# motorController.net
KiCad netlist of a schematic drawn in Altium Designer
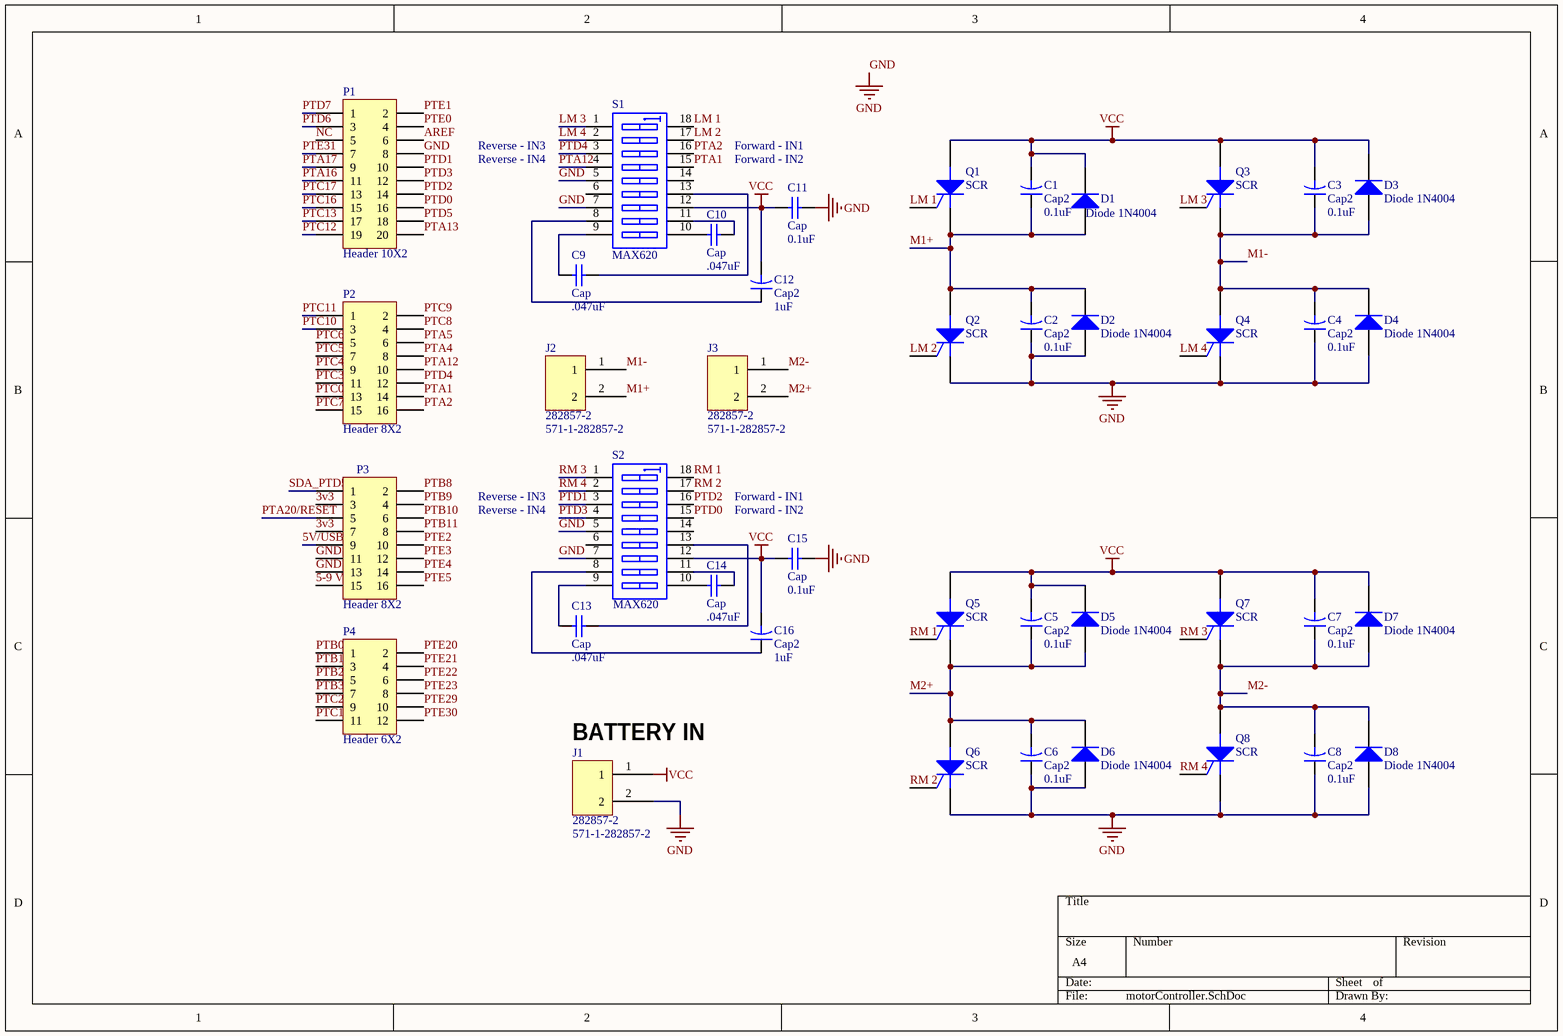
[diagram p0: motorController.SchDoc]

(export (version "E")
  (design (tool "Eeschema 10.0.6"))
  (components
    (comp (ref "C1")
      (value "Cap2")
      (footprint "CAPR5-4X5")
      (description "Capacitor")
      (fields (field (name "ALTIUM_VALUE") "0.1uF") (field (name "PUBLISHER") "Altium Limited"))
      (libsource (lib "Miscellaneous Devices") (part "Cap2"))
    )
    (comp (ref "C2")
      (value "Cap2")
      (footprint "CAPR5-4X5")
      (description "Capacitor")
      (fields (field (name "ALTIUM_VALUE") "0.1uF") (field (name "PUBLISHER") "Altium Limited"))
      (libsource (lib "Miscellaneous Devices") (part "Cap2"))
    )
    (comp (ref "C3")
      (value "Cap2")
      (footprint "CAPR5-4X5")
      (description "Capacitor")
      (fields (field (name "ALTIUM_VALUE") "0.1uF") (field (name "PUBLISHER") "Altium Limited"))
      (libsource (lib "Miscellaneous Devices") (part "Cap2"))
    )
    (comp (ref "C4")
      (value "Cap2")
      (footprint "CAPR5-4X5")
      (description "Capacitor")
      (fields (field (name "ALTIUM_VALUE") "0.1uF") (field (name "PUBLISHER") "Altium Limited"))
      (libsource (lib "Miscellaneous Devices") (part "Cap2"))
    )
    (comp (ref "C5")
      (value "Cap2")
      (footprint "CAPR5-4X5")
      (description "Capacitor")
      (fields (field (name "ALTIUM_VALUE") "0.1uF") (field (name "PUBLISHER") "Altium Limited"))
      (libsource (lib "Miscellaneous Devices") (part "Cap2"))
    )
    (comp (ref "C6")
      (value "Cap2")
      (footprint "CAPR5-4X5")
      (description "Capacitor")
      (fields (field (name "ALTIUM_VALUE") "0.1uF") (field (name "PUBLISHER") "Altium Limited"))
      (libsource (lib "Miscellaneous Devices") (part "Cap2"))
    )
    (comp (ref "C7")
      (value "Cap2")
      (footprint "CAPR5-4X5")
      (description "Capacitor")
      (fields (field (name "ALTIUM_VALUE") "0.1uF") (field (name "PUBLISHER") "Altium Limited"))
      (libsource (lib "Miscellaneous Devices") (part "Cap2"))
    )
    (comp (ref "C8")
      (value "Cap2")
      (footprint "CAPR5-4X5")
      (description "Capacitor")
      (fields (field (name "ALTIUM_VALUE") "0.1uF") (field (name "PUBLISHER") "Altium Limited"))
      (libsource (lib "Miscellaneous Devices") (part "Cap2"))
    )
    (comp (ref "C9")
      (value "Cap")
      (footprint "RAD-0.3")
      (description "Capacitor")
      (fields (field (name "ALTIUM_VALUE") ".047uF") (field (name "PUBLISHER") "Altium Limited"))
      (libsource (lib "Miscellaneous Devices") (part "Cap"))
    )
    (comp (ref "C10")
      (value "Cap")
      (footprint "RAD-0.3")
      (description "Capacitor")
      (fields (field (name "ALTIUM_VALUE") ".047uF") (field (name "PUBLISHER") "Altium Limited"))
      (libsource (lib "Miscellaneous Devices") (part "Cap"))
    )
    (comp (ref "C11")
      (value "Cap")
      (footprint "RAD-0.3")
      (description "Capacitor")
      (fields (field (name "ALTIUM_VALUE") "0.1uF") (field (name "PUBLISHER") "Altium Limited"))
      (libsource (lib "Miscellaneous Devices") (part "Cap"))
    )
    (comp (ref "C12")
      (value "Cap2")
      (footprint "CAPR5-4X5")
      (description "Capacitor")
      (fields (field (name "ALTIUM_VALUE") "1uF") (field (name "PUBLISHER") "Altium Limited"))
      (libsource (lib "Miscellaneous Devices") (part "Cap2"))
    )
    (comp (ref "C13")
      (value "Cap")
      (footprint "RAD-0.3")
      (description "Capacitor")
      (fields (field (name "ALTIUM_VALUE") ".047uF") (field (name "PUBLISHER") "Altium Limited"))
      (libsource (lib "Miscellaneous Devices") (part "Cap"))
    )
    (comp (ref "C14")
      (value "Cap")
      (footprint "RAD-0.3")
      (description "Capacitor")
      (fields (field (name "ALTIUM_VALUE") ".047uF") (field (name "PUBLISHER") "Altium Limited"))
      (libsource (lib "Miscellaneous Devices") (part "Cap"))
    )
    (comp (ref "C15")
      (value "Cap")
      (footprint "RAD-0.3")
      (description "Capacitor")
      (fields (field (name "ALTIUM_VALUE") "0.1uF") (field (name "PUBLISHER") "Altium Limited"))
      (libsource (lib "Miscellaneous Devices") (part "Cap"))
    )
    (comp (ref "C16")
      (value "Cap2")
      (footprint "CAPR5-4X5")
      (description "Capacitor")
      (fields (field (name "ALTIUM_VALUE") "1uF") (field (name "PUBLISHER") "Altium Limited"))
      (libsource (lib "Miscellaneous Devices") (part "Cap2"))
    )
    (comp (ref "D1")
      (value "Diode 1N4004")
      (footprint "DO-41")
      (description "1 Amp General Purpose Rectifier")
      (fields (field (name "PUBLISHER") "Altium Limited"))
      (libsource (lib "Miscellaneous Devices") (part "Diode 1N4004"))
    )
    (comp (ref "D2")
      (value "Diode 1N4004")
      (footprint "DO-41")
      (description "1 Amp General Purpose Rectifier")
      (fields (field (name "PUBLISHER") "Altium Limited"))
      (libsource (lib "Miscellaneous Devices") (part "Diode 1N4004"))
    )
    (comp (ref "D3")
      (value "Diode 1N4004")
      (footprint "DO-41")
      (description "1 Amp General Purpose Rectifier")
      (fields (field (name "PUBLISHER") "Altium Limited"))
      (libsource (lib "Miscellaneous Devices") (part "Diode 1N4004"))
    )
    (comp (ref "D4")
      (value "Diode 1N4004")
      (footprint "DO-41")
      (description "1 Amp General Purpose Rectifier")
      (fields (field (name "PUBLISHER") "Altium Limited"))
      (libsource (lib "Miscellaneous Devices") (part "Diode 1N4004"))
    )
    (comp (ref "D5")
      (value "Diode 1N4004")
      (footprint "DO-41")
      (description "1 Amp General Purpose Rectifier")
      (fields (field (name "PUBLISHER") "Altium Limited"))
      (libsource (lib "Miscellaneous Devices") (part "Diode 1N4004"))
    )
    (comp (ref "D6")
      (value "Diode 1N4004")
      (footprint "DO-41")
      (description "1 Amp General Purpose Rectifier")
      (fields (field (name "PUBLISHER") "Altium Limited"))
      (libsource (lib "Miscellaneous Devices") (part "Diode 1N4004"))
    )
    (comp (ref "D7")
      (value "Diode 1N4004")
      (footprint "DO-41")
      (description "1 Amp General Purpose Rectifier")
      (fields (field (name "PUBLISHER") "Altium Limited"))
      (libsource (lib "Miscellaneous Devices") (part "Diode 1N4004"))
    )
    (comp (ref "D8")
      (value "Diode 1N4004")
      (footprint "DO-41")
      (description "1 Amp General Purpose Rectifier")
      (fields (field (name "PUBLISHER") "Altium Limited"))
      (libsource (lib "Miscellaneous Devices") (part "Diode 1N4004"))
    )
    (comp (ref "J1")
      (value "282857-2")
      (footprint "282857-2")
      (fields (field (name "SUPPLIER PART NUMBER 1") "571-1-282857-2"))
      (libsource (lib "TE_Connectors") (part "282857-2"))
    )
    (comp (ref "J2")
      (value "282857-2")
      (footprint "282857-2")
      (fields (field (name "SUPPLIER PART NUMBER 1") "571-1-282857-2"))
      (libsource (lib "TE_Connectors") (part "282857-2"))
    )
    (comp (ref "J3")
      (value "282857-2")
      (footprint "282857-2")
      (fields (field (name "SUPPLIER PART NUMBER 1") "571-1-282857-2"))
      (libsource (lib "TE_Connectors") (part "282857-2"))
    )
    (comp (ref "P1")
      (value "Header 10X2")
      (footprint "HDR2X10")
      (description "Header, 10-Pin, Dual row")
      (fields (field (name "PUBLISHER") "Altium Limited"))
      (libsource (lib "Miscellaneous Connectors") (part "Header 10X2"))
    )
    (comp (ref "P2")
      (value "Header 8X2")
      (footprint "HDR2X8")
      (description "Header, 8-Pin, Dual row")
      (fields (field (name "PUBLISHER") "Altium Limited"))
      (libsource (lib "Miscellaneous Connectors") (part "Header 8X2"))
    )
    (comp (ref "P3")
      (value "Header 8X2")
      (footprint "HDR2X8")
      (description "Header, 8-Pin, Dual row")
      (fields (field (name "PUBLISHER") "Altium Limited"))
      (libsource (lib "Miscellaneous Connectors") (part "Header 8X2"))
    )
    (comp (ref "P4")
      (value "Header 6X2")
      (footprint "HDR2X6")
      (description "Header, 6-Pin, Dual row")
      (fields (field (name "PUBLISHER") "Altium Limited"))
      (libsource (lib "Miscellaneous Connectors") (part "Header 6X2"))
    )
    (comp (ref "Q1")
      (value "SCR")
      (footprint "TO-220-AB")
      (description "Silicon Controlled Rectifier")
      (fields (field (name "PUBLISHER") "Altium Limited"))
      (libsource (lib "Miscellaneous Devices") (part "SCR"))
    )
    (comp (ref "Q2")
      (value "SCR")
      (footprint "TO-220-AB")
      (description "Silicon Controlled Rectifier")
      (fields (field (name "PUBLISHER") "Altium Limited"))
      (libsource (lib "Miscellaneous Devices") (part "SCR"))
    )
    (comp (ref "Q3")
      (value "SCR")
      (footprint "TO-220-AB")
      (description "Silicon Controlled Rectifier")
      (fields (field (name "PUBLISHER") "Altium Limited"))
      (libsource (lib "Miscellaneous Devices") (part "SCR"))
    )
    (comp (ref "Q4")
      (value "SCR")
      (footprint "TO-220-AB")
      (description "Silicon Controlled Rectifier")
      (fields (field (name "PUBLISHER") "Altium Limited"))
      (libsource (lib "Miscellaneous Devices") (part "SCR"))
    )
    (comp (ref "Q5")
      (value "SCR")
      (footprint "TO-220-AB")
      (description "Silicon Controlled Rectifier")
      (fields (field (name "PUBLISHER") "Altium Limited"))
      (libsource (lib "Miscellaneous Devices") (part "SCR"))
    )
    (comp (ref "Q6")
      (value "SCR")
      (footprint "TO-220-AB")
      (description "Silicon Controlled Rectifier")
      (fields (field (name "PUBLISHER") "Altium Limited"))
      (libsource (lib "Miscellaneous Devices") (part "SCR"))
    )
    (comp (ref "Q7")
      (value "SCR")
      (footprint "TO-220-AB")
      (description "Silicon Controlled Rectifier")
      (fields (field (name "PUBLISHER") "Altium Limited"))
      (libsource (lib "Miscellaneous Devices") (part "SCR"))
    )
    (comp (ref "Q8")
      (value "SCR")
      (footprint "TO-220-AB")
      (description "Silicon Controlled Rectifier")
      (fields (field (name "PUBLISHER") "Altium Limited"))
      (libsource (lib "Miscellaneous Devices") (part "SCR"))
    )
    (comp (ref "S1")
      (value "MAX620")
      (footprint "DIP-18")
      (description "DIP Switch, 9 Position, SPST")
      (fields (field (name "PUBLISHER") "Altium Limited"))
      (libsource (lib "Miscellaneous Devices") (part "SW DIP-9"))
    )
    (comp (ref "S2")
      (value "MAX620")
      (footprint "DIP-18")
      (description "DIP Switch, 9 Position, SPST")
      (fields (field (name "PUBLISHER") "Altium Limited"))
      (libsource (lib "Miscellaneous Devices") (part "SW DIP-9"))
    )
  )
  (nets
    (net (code "1") (name "/3v3") (class "Default")
      (node (ref "P3") (pin "3") (pinfunction "3_3") (pintype "passive"))
      (node (ref "P3") (pin "7") (pinfunction "7_7") (pintype "passive"))
    )
    (net (code "2") (name "/5-9 Vin") (class "Default")
      (node (ref "P3") (pin "15") (pinfunction "15_15") (pintype "passive"))
    )
    (net (code "3") (name "/5V{slash}USB") (class "Default")
      (node (ref "P3") (pin "9") (pinfunction "9_9") (pintype "passive"))
    )
    (net (code "4") (name "/AREF") (class "Default")
      (node (ref "P1") (pin "6") (pinfunction "6_6") (pintype "passive"))
    )
    (net (code "5") (name "/LM 1") (class "Default")
      (node (ref "Q1") (pin "2") (pinfunction "G_2") (pintype "passive"))
      (node (ref "S1") (pin "18") (pinfunction "B1_18") (pintype "passive"))
    )
    (net (code "6") (name "/LM 2") (class "Default")
      (node (ref "Q2") (pin "2") (pinfunction "G_2") (pintype "passive"))
      (node (ref "S1") (pin "17") (pinfunction "B2_17") (pintype "passive"))
    )
    (net (code "7") (name "/LM 3") (class "Default")
      (node (ref "Q3") (pin "2") (pinfunction "G_2") (pintype "passive"))
      (node (ref "S1") (pin "1") (pinfunction "A1_1") (pintype "passive"))
    )
    (net (code "8") (name "/LM 4") (class "Default")
      (node (ref "Q4") (pin "2") (pinfunction "G_2") (pintype "passive"))
      (node (ref "S1") (pin "2") (pinfunction "A2_2") (pintype "passive"))
    )
    (net (code "9") (name "/M1+") (class "Default")
      (node (ref "C1") (pin "1") (pinfunction "1_1") (pintype "passive"))
      (node (ref "C2") (pin "2") (pinfunction "2_2") (pintype "passive"))
      (node (ref "D1") (pin "1") (pinfunction "A_1") (pintype "passive"))
      (node (ref "D2") (pin "2") (pinfunction "K_2") (pintype "passive"))
      (node (ref "J2") (pin "2") (pinfunction "2_2") (pintype "passive"))
      (node (ref "Q1") (pin "3") (pinfunction "K_3") (pintype "passive"))
      (node (ref "Q2") (pin "1") (pinfunction "A_1") (pintype "passive"))
    )
    (net (code "10") (name "/M1-") (class "Default")
      (node (ref "C3") (pin "1") (pinfunction "1_1") (pintype "passive"))
      (node (ref "C4") (pin "2") (pinfunction "2_2") (pintype "passive"))
      (node (ref "D3") (pin "1") (pinfunction "A_1") (pintype "passive"))
      (node (ref "D4") (pin "2") (pinfunction "K_2") (pintype "passive"))
      (node (ref "J2") (pin "1") (pinfunction "1_1") (pintype "passive"))
      (node (ref "Q3") (pin "3") (pinfunction "K_3") (pintype "passive"))
      (node (ref "Q4") (pin "1") (pinfunction "A_1") (pintype "passive"))
    )
    (net (code "11") (name "/M2+") (class "Default")
      (node (ref "C5") (pin "1") (pinfunction "1_1") (pintype "passive"))
      (node (ref "C6") (pin "2") (pinfunction "2_2") (pintype "passive"))
      (node (ref "D5") (pin "1") (pinfunction "A_1") (pintype "passive"))
      (node (ref "D6") (pin "2") (pinfunction "K_2") (pintype "passive"))
      (node (ref "J3") (pin "2") (pinfunction "2_2") (pintype "passive"))
      (node (ref "Q5") (pin "3") (pinfunction "K_3") (pintype "passive"))
      (node (ref "Q6") (pin "1") (pinfunction "A_1") (pintype "passive"))
    )
    (net (code "12") (name "/M2-") (class "Default")
      (node (ref "C7") (pin "1") (pinfunction "1_1") (pintype "passive"))
      (node (ref "C8") (pin "2") (pinfunction "2_2") (pintype "passive"))
      (node (ref "D7") (pin "1") (pinfunction "A_1") (pintype "passive"))
      (node (ref "D8") (pin "2") (pinfunction "K_2") (pintype "passive"))
      (node (ref "J3") (pin "1") (pinfunction "1_1") (pintype "passive"))
      (node (ref "Q7") (pin "3") (pinfunction "K_3") (pintype "passive"))
      (node (ref "Q8") (pin "1") (pinfunction "A_1") (pintype "passive"))
    )
    (net (code "13") (name "/NC") (class "Default")
      (node (ref "P1") (pin "5") (pinfunction "5_5") (pintype "passive"))
    )
    (net (code "14") (name "/PTA1") (class "Default")
      (node (ref "P2") (pin "14") (pinfunction "14_14") (pintype "passive"))
      (node (ref "S1") (pin "15") (pinfunction "B4_15") (pintype "passive"))
    )
    (net (code "15") (name "/PTA2") (class "Default")
      (node (ref "P2") (pin "16") (pinfunction "16_16") (pintype "passive"))
      (node (ref "S1") (pin "16") (pinfunction "B3_16") (pintype "passive"))
    )
    (net (code "16") (name "/PTA4") (class "Default")
      (node (ref "P2") (pin "8") (pinfunction "8_8") (pintype "passive"))
    )
    (net (code "17") (name "/PTA5") (class "Default")
      (node (ref "P2") (pin "6") (pinfunction "6_6") (pintype "passive"))
    )
    (net (code "18") (name "/PTA12") (class "Default")
      (node (ref "P2") (pin "10") (pinfunction "10_10") (pintype "passive"))
      (node (ref "S1") (pin "4") (pinfunction "A4_4") (pintype "passive"))
    )
    (net (code "19") (name "/PTA13") (class "Default")
      (node (ref "P1") (pin "20") (pinfunction "20_20") (pintype "passive"))
    )
    (net (code "20") (name "/PTA16") (class "Default")
      (node (ref "P1") (pin "11") (pinfunction "11_11") (pintype "passive"))
    )
    (net (code "21") (name "/PTA17") (class "Default")
      (node (ref "P1") (pin "9") (pinfunction "9_9") (pintype "passive"))
    )
    (net (code "22") (name "/PTA20{slash}RESET") (class "Default")
      (node (ref "P3") (pin "5") (pinfunction "5_5") (pintype "passive"))
    )
    (net (code "23") (name "/PTB0") (class "Default")
      (node (ref "P4") (pin "1") (pinfunction "1_1") (pintype "passive"))
    )
    (net (code "24") (name "/PTB1") (class "Default")
      (node (ref "P4") (pin "3") (pinfunction "3_3") (pintype "passive"))
    )
    (net (code "25") (name "/PTB2") (class "Default")
      (node (ref "P4") (pin "5") (pinfunction "5_5") (pintype "passive"))
    )
    (net (code "26") (name "/PTB3") (class "Default")
      (node (ref "P4") (pin "7") (pinfunction "7_7") (pintype "passive"))
    )
    (net (code "27") (name "/PTB8") (class "Default")
      (node (ref "P3") (pin "2") (pinfunction "2_2") (pintype "passive"))
    )
    (net (code "28") (name "/PTB9") (class "Default")
      (node (ref "P3") (pin "4") (pinfunction "4_4") (pintype "passive"))
    )
    (net (code "29") (name "/PTB10") (class "Default")
      (node (ref "P3") (pin "6") (pinfunction "6_6") (pintype "passive"))
    )
    (net (code "30") (name "/PTB11") (class "Default")
      (node (ref "P3") (pin "8") (pinfunction "8_8") (pintype "passive"))
    )
    (net (code "31") (name "/PTC0") (class "Default")
      (node (ref "P2") (pin "13") (pinfunction "13_13") (pintype "passive"))
    )
    (net (code "32") (name "/PTC1") (class "Default")
      (node (ref "P4") (pin "11") (pinfunction "11_11") (pintype "passive"))
    )
    (net (code "33") (name "/PTC2") (class "Default")
      (node (ref "P4") (pin "9") (pinfunction "9_9") (pintype "passive"))
    )
    (net (code "34") (name "/PTC3") (class "Default")
      (node (ref "P2") (pin "11") (pinfunction "11_11") (pintype "passive"))
    )
    (net (code "35") (name "/PTC4") (class "Default")
      (node (ref "P2") (pin "9") (pinfunction "9_9") (pintype "passive"))
    )
    (net (code "36") (name "/PTC5") (class "Default")
      (node (ref "P2") (pin "7") (pinfunction "7_7") (pintype "passive"))
    )
    (net (code "37") (name "/PTC6") (class "Default")
      (node (ref "P2") (pin "5") (pinfunction "5_5") (pintype "passive"))
    )
    (net (code "38") (name "/PTC7") (class "Default")
      (node (ref "P2") (pin "15") (pinfunction "15_15") (pintype "passive"))
    )
    (net (code "39") (name "/PTC8") (class "Default")
      (node (ref "P2") (pin "4") (pinfunction "4_4") (pintype "passive"))
    )
    (net (code "40") (name "/PTC9") (class "Default")
      (node (ref "P2") (pin "2") (pinfunction "2_2") (pintype "passive"))
    )
    (net (code "41") (name "/PTC10") (class "Default")
      (node (ref "P2") (pin "3") (pinfunction "3_3") (pintype "passive"))
    )
    (net (code "42") (name "/PTC11") (class "Default")
      (node (ref "P2") (pin "1") (pinfunction "1_1") (pintype "passive"))
    )
    (net (code "43") (name "/PTC12") (class "Default")
      (node (ref "P1") (pin "19") (pinfunction "19_19") (pintype "passive"))
    )
    (net (code "44") (name "/PTC13") (class "Default")
      (node (ref "P1") (pin "17") (pinfunction "17_17") (pintype "passive"))
    )
    (net (code "45") (name "/PTC16") (class "Default")
      (node (ref "P1") (pin "15") (pinfunction "15_15") (pintype "passive"))
    )
    (net (code "46") (name "/PTC17") (class "Default")
      (node (ref "P1") (pin "13") (pinfunction "13_13") (pintype "passive"))
    )
    (net (code "47") (name "/PTD0") (class "Default")
      (node (ref "P1") (pin "16") (pinfunction "16_16") (pintype "passive"))
      (node (ref "S2") (pin "15") (pinfunction "B4_15") (pintype "passive"))
    )
    (net (code "48") (name "/PTD1") (class "Default")
      (node (ref "P1") (pin "10") (pinfunction "10_10") (pintype "passive"))
      (node (ref "S2") (pin "3") (pinfunction "A3_3") (pintype "passive"))
    )
    (net (code "49") (name "/PTD2") (class "Default")
      (node (ref "P1") (pin "14") (pinfunction "14_14") (pintype "passive"))
      (node (ref "S2") (pin "16") (pinfunction "B3_16") (pintype "passive"))
    )
    (net (code "50") (name "/PTD3") (class "Default")
      (node (ref "P1") (pin "12") (pinfunction "12_12") (pintype "passive"))
      (node (ref "S2") (pin "4") (pinfunction "A4_4") (pintype "passive"))
    )
    (net (code "51") (name "/PTD4") (class "Default")
      (node (ref "P2") (pin "12") (pinfunction "12_12") (pintype "passive"))
      (node (ref "S1") (pin "3") (pinfunction "A3_3") (pintype "passive"))
    )
    (net (code "52") (name "/PTD5") (class "Default")
      (node (ref "P1") (pin "18") (pinfunction "18_18") (pintype "passive"))
    )
    (net (code "53") (name "/PTD6") (class "Default")
      (node (ref "P1") (pin "3") (pinfunction "3_3") (pintype "passive"))
    )
    (net (code "54") (name "/PTD7") (class "Default")
      (node (ref "P1") (pin "1") (pinfunction "1_1") (pintype "passive"))
    )
    (net (code "55") (name "/PTE0") (class "Default")
      (node (ref "P1") (pin "4") (pinfunction "4_4") (pintype "passive"))
    )
    (net (code "56") (name "/PTE1") (class "Default")
      (node (ref "P1") (pin "2") (pinfunction "2_2") (pintype "passive"))
    )
    (net (code "57") (name "/PTE2") (class "Default")
      (node (ref "P3") (pin "10") (pinfunction "10_10") (pintype "passive"))
    )
    (net (code "58") (name "/PTE3") (class "Default")
      (node (ref "P3") (pin "12") (pinfunction "12_12") (pintype "passive"))
    )
    (net (code "59") (name "/PTE4") (class "Default")
      (node (ref "P3") (pin "14") (pinfunction "14_14") (pintype "passive"))
    )
    (net (code "60") (name "/PTE5") (class "Default")
      (node (ref "P3") (pin "16") (pinfunction "16_16") (pintype "passive"))
    )
    (net (code "61") (name "/PTE20") (class "Default")
      (node (ref "P4") (pin "2") (pinfunction "2_2") (pintype "passive"))
    )
    (net (code "62") (name "/PTE21") (class "Default")
      (node (ref "P4") (pin "4") (pinfunction "4_4") (pintype "passive"))
    )
    (net (code "63") (name "/PTE22") (class "Default")
      (node (ref "P4") (pin "6") (pinfunction "6_6") (pintype "passive"))
    )
    (net (code "64") (name "/PTE23") (class "Default")
      (node (ref "P4") (pin "8") (pinfunction "8_8") (pintype "passive"))
    )
    (net (code "65") (name "/PTE29") (class "Default")
      (node (ref "P4") (pin "10") (pinfunction "10_10") (pintype "passive"))
    )
    (net (code "66") (name "/PTE30") (class "Default")
      (node (ref "P4") (pin "12") (pinfunction "12_12") (pintype "passive"))
    )
    (net (code "67") (name "/PTE31") (class "Default")
      (node (ref "P1") (pin "7") (pinfunction "7_7") (pintype "passive"))
    )
    (net (code "68") (name "/RM 1") (class "Default")
      (node (ref "Q5") (pin "2") (pinfunction "G_2") (pintype "passive"))
      (node (ref "S2") (pin "18") (pinfunction "B1_18") (pintype "passive"))
    )
    (net (code "69") (name "/RM 2") (class "Default")
      (node (ref "Q6") (pin "2") (pinfunction "G_2") (pintype "passive"))
      (node (ref "S2") (pin "17") (pinfunction "B2_17") (pintype "passive"))
    )
    (net (code "70") (name "/RM 3") (class "Default")
      (node (ref "Q7") (pin "2") (pinfunction "G_2") (pintype "passive"))
      (node (ref "S2") (pin "1") (pinfunction "A1_1") (pintype "passive"))
    )
    (net (code "71") (name "/RM 4") (class "Default")
      (node (ref "Q8") (pin "2") (pinfunction "G_2") (pintype "passive"))
      (node (ref "S2") (pin "2") (pinfunction "A2_2") (pintype "passive"))
    )
    (net (code "72") (name "/SDA_PTD5") (class "Default")
      (node (ref "P3") (pin "1") (pinfunction "1_1") (pintype "passive"))
    )
    (net (code "73") (name "GND") (class "Default")
      (node (ref "C11") (pin "2") (pinfunction "2_2") (pintype "passive"))
      (node (ref "C15") (pin "2") (pinfunction "2_2") (pintype "passive"))
      (node (ref "C2") (pin "1") (pinfunction "1_1") (pintype "passive"))
      (node (ref "C4") (pin "1") (pinfunction "1_1") (pintype "passive"))
      (node (ref "C6") (pin "1") (pinfunction "1_1") (pintype "passive"))
      (node (ref "C8") (pin "1") (pinfunction "1_1") (pintype "passive"))
      (node (ref "D2") (pin "1") (pinfunction "A_1") (pintype "passive"))
      (node (ref "D4") (pin "1") (pinfunction "A_1") (pintype "passive"))
      (node (ref "D6") (pin "1") (pinfunction "A_1") (pintype "passive"))
      (node (ref "D8") (pin "1") (pinfunction "A_1") (pintype "passive"))
      (node (ref "J1") (pin "2") (pinfunction "2_2") (pintype "passive"))
      (node (ref "P1") (pin "8") (pinfunction "8_8") (pintype "passive"))
      (node (ref "P3") (pin "11") (pinfunction "11_11") (pintype "passive"))
      (node (ref "P3") (pin "13") (pinfunction "13_13") (pintype "passive"))
      (node (ref "Q2") (pin "3") (pinfunction "K_3") (pintype "passive"))
      (node (ref "Q4") (pin "3") (pinfunction "K_3") (pintype "passive"))
      (node (ref "Q6") (pin "3") (pinfunction "K_3") (pintype "passive"))
      (node (ref "Q8") (pin "3") (pinfunction "K_3") (pintype "passive"))
      (node (ref "S1") (pin "5") (pinfunction "A5_5") (pintype "passive"))
      (node (ref "S1") (pin "7") (pinfunction "A7_7") (pintype "passive"))
      (node (ref "S2") (pin "5") (pinfunction "A5_5") (pintype "passive"))
      (node (ref "S2") (pin "7") (pinfunction "A7_7") (pintype "passive"))
    )
    (net (code "74") (name "Net-(S1-A8)") (class "Default")
      (node (ref "C12") (pin "1") (pinfunction "1_1") (pintype "passive"))
      (node (ref "S1") (pin "8") (pinfunction "A8_8") (pintype "passive"))
    )
    (net (code "75") (name "Net-(S1-A9)") (class "Default")
      (node (ref "C9") (pin "1") (pinfunction "1_1") (pintype "passive"))
      (node (ref "S1") (pin "9") (pinfunction "A9_9") (pintype "passive"))
    )
    (net (code "76") (name "Net-(S1-B6)") (class "Default")
      (node (ref "C9") (pin "2") (pinfunction "2_2") (pintype "passive"))
      (node (ref "S1") (pin "13") (pinfunction "B6_13") (pintype "passive"))
    )
    (net (code "77") (name "Net-(S1-B8)") (class "Default")
      (node (ref "C10") (pin "2") (pinfunction "2_2") (pintype "passive"))
      (node (ref "S1") (pin "11") (pinfunction "B8_11") (pintype "passive"))
    )
    (net (code "78") (name "Net-(S1-B9)") (class "Default")
      (node (ref "C10") (pin "1") (pinfunction "1_1") (pintype "passive"))
      (node (ref "S1") (pin "10") (pinfunction "B9_10") (pintype "passive"))
    )
    (net (code "79") (name "Net-(S2-A8)") (class "Default")
      (node (ref "C16") (pin "1") (pinfunction "1_1") (pintype "passive"))
      (node (ref "S2") (pin "8") (pinfunction "A8_8") (pintype "passive"))
    )
    (net (code "80") (name "Net-(S2-A9)") (class "Default")
      (node (ref "C13") (pin "1") (pinfunction "1_1") (pintype "passive"))
      (node (ref "S2") (pin "9") (pinfunction "A9_9") (pintype "passive"))
    )
    (net (code "81") (name "Net-(S2-B6)") (class "Default")
      (node (ref "C13") (pin "2") (pinfunction "2_2") (pintype "passive"))
      (node (ref "S2") (pin "13") (pinfunction "B6_13") (pintype "passive"))
    )
    (net (code "82") (name "Net-(S2-B8)") (class "Default")
      (node (ref "C14") (pin "2") (pinfunction "2_2") (pintype "passive"))
      (node (ref "S2") (pin "11") (pinfunction "B8_11") (pintype "passive"))
    )
    (net (code "83") (name "Net-(S2-B9)") (class "Default")
      (node (ref "C14") (pin "1") (pinfunction "1_1") (pintype "passive"))
      (node (ref "S2") (pin "10") (pinfunction "B9_10") (pintype "passive"))
    )
    (net (code "84") (name "VCC") (class "Default")
      (node (ref "C1") (pin "2") (pinfunction "2_2") (pintype "passive"))
      (node (ref "C11") (pin "1") (pinfunction "1_1") (pintype "passive"))
      (node (ref "C12") (pin "2") (pinfunction "2_2") (pintype "passive"))
      (node (ref "C15") (pin "1") (pinfunction "1_1") (pintype "passive"))
      (node (ref "C16") (pin "2") (pinfunction "2_2") (pintype "passive"))
      (node (ref "C3") (pin "2") (pinfunction "2_2") (pintype "passive"))
      (node (ref "C5") (pin "2") (pinfunction "2_2") (pintype "passive"))
      (node (ref "C7") (pin "2") (pinfunction "2_2") (pintype "passive"))
      (node (ref "D1") (pin "2") (pinfunction "K_2") (pintype "passive"))
      (node (ref "D3") (pin "2") (pinfunction "K_2") (pintype "passive"))
      (node (ref "D5") (pin "2") (pinfunction "K_2") (pintype "passive"))
      (node (ref "D7") (pin "2") (pinfunction "K_2") (pintype "passive"))
      (node (ref "J1") (pin "1") (pinfunction "1_1") (pintype "passive"))
      (node (ref "Q1") (pin "1") (pinfunction "A_1") (pintype "passive"))
      (node (ref "Q3") (pin "1") (pinfunction "A_1") (pintype "passive"))
      (node (ref "Q5") (pin "1") (pinfunction "A_1") (pintype "passive"))
      (node (ref "Q7") (pin "1") (pinfunction "A_1") (pintype "passive"))
      (node (ref "S1") (pin "12") (pinfunction "B7_12") (pintype "passive"))
      (node (ref "S2") (pin "12") (pinfunction "B7_12") (pintype "passive"))
    )
    (net (code "85") (name "unconnected-(S1-A6-Pad6)") (class "Default")
      (node (ref "S1") (pin "6") (pinfunction "A6_6") (pintype "passive"))
    )
    (net (code "86") (name "unconnected-(S1-B5-Pad14)") (class "Default")
      (node (ref "S1") (pin "14") (pinfunction "B5_14") (pintype "passive"))
    )
    (net (code "87") (name "unconnected-(S2-A6-Pad6)") (class "Default")
      (node (ref "S2") (pin "6") (pinfunction "A6_6") (pintype "passive"))
    )
    (net (code "88") (name "unconnected-(S2-B5-Pad14)") (class "Default")
      (node (ref "S2") (pin "14") (pinfunction "B5_14") (pintype "passive"))
    )
  )
)
